# Front_Servo_Supply.net
KiCad netlist of a schematic drawn in Altium Designer
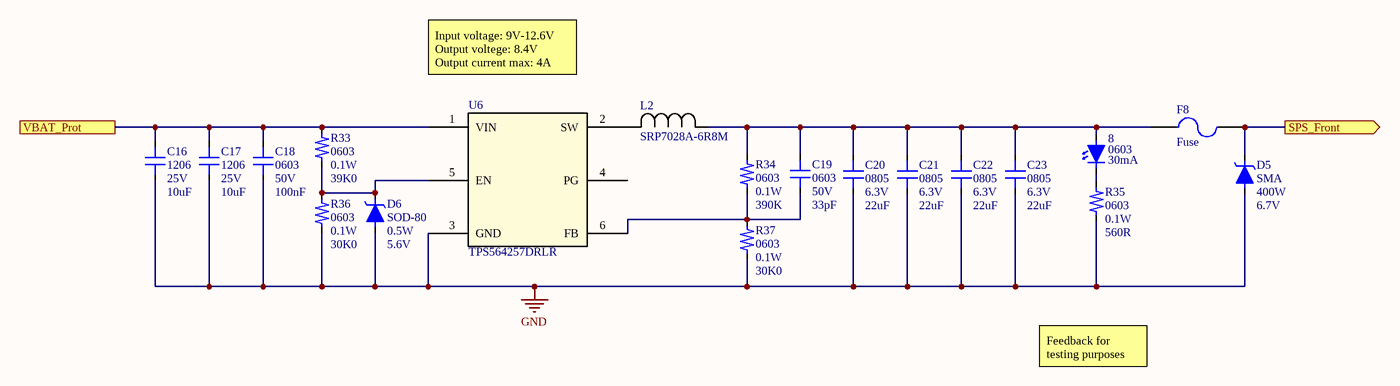
[diagram p0: Front_Servo_Supply.SchDoc]

(export (version "E")
  (design (tool "Eeschema 10.0.6"))
  (components
    (comp (ref "8")
      (value "0603")
      (footprint "LED_0603")
      (fields
        (field (name "PART NUMBER") "FYLS-0603UGC")
        (field (name "TOLERANCE") "5%")
        (field (name "RATING") "30mA")
      )
      (libsource (lib "Components") (part "Diode_LED"))
    )
    (comp (ref "C16")
      (value "1206")
      (footprint "C_1206")
      (fields
        (field (name "TOLERANCE") "10%")
        (field (name "PART NUMBER") "C3216X7R1E106K160AB")
        (field (name "RATING") "25V")
        (field (name "ALTIUM_VALUE") "10uF")
      )
      (libsource (lib "Components") (part "Capacitor_Chip"))
    )
    (comp (ref "C17")
      (value "1206")
      (footprint "C_1206")
      (fields
        (field (name "TOLERANCE") "10%")
        (field (name "PART NUMBER") "C3216X7R1E106K160AB")
        (field (name "RATING") "25V")
        (field (name "ALTIUM_VALUE") "10uF")
      )
      (libsource (lib "Components") (part "Capacitor_Chip"))
    )
    (comp (ref "C18")
      (value "0603")
      (footprint "C_0603")
      (fields
        (field (name "TOLERANCE") "10%")
        (field (name "PART NUMBER") "CC0603KRX7R9BB104")
        (field (name "RATING") "50V")
        (field (name "ALTIUM_VALUE") "100nF")
        (field (name "NI PART NUMBER") "716340-01")
      )
      (libsource (lib "Components") (part "Capacitor_Chip"))
    )
    (comp (ref "C19")
      (value "0603")
      (footprint "C_0603")
      (fields
        (field (name "TOLERANCE") "5%")
        (field (name "PART NUMBER") "CL10C330JB8NNNC")
        (field (name "RATING") "50V")
        (field (name "ALTIUM_VALUE") "33pF")
        (field (name "NI PART NUMBER") "715511-01")
      )
      (libsource (lib "Components") (part "Capacitor_Chip"))
    )
    (comp (ref "C20")
      (value "0805")
      (footprint "C_0805")
      (fields
        (field (name "TOLERANCE") "20%")
        (field (name "PART NUMBER") "CL21A226MQQNNNG")
        (field (name "RATING") "6.3V")
        (field (name "ALTIUM_VALUE") "22uF")
      )
      (libsource (lib "Components") (part "Capacitor_Chip"))
    )
    (comp (ref "C21")
      (value "0805")
      (footprint "C_0805")
      (fields
        (field (name "TOLERANCE") "20%")
        (field (name "PART NUMBER") "CL21A226MQQNNNG")
        (field (name "RATING") "6.3V")
        (field (name "ALTIUM_VALUE") "22uF")
      )
      (libsource (lib "Components") (part "Capacitor_Chip"))
    )
    (comp (ref "C22")
      (value "0805")
      (footprint "C_0805")
      (fields
        (field (name "TOLERANCE") "20%")
        (field (name "PART NUMBER") "CL21A226MQQNNNG")
        (field (name "RATING") "6.3V")
        (field (name "ALTIUM_VALUE") "22uF")
      )
      (libsource (lib "Components") (part "Capacitor_Chip"))
    )
    (comp (ref "C23")
      (value "0805")
      (footprint "C_0805")
      (fields
        (field (name "TOLERANCE") "20%")
        (field (name "PART NUMBER") "CL21A226MQQNNNG")
        (field (name "RATING") "6.3V")
        (field (name "ALTIUM_VALUE") "22uF")
      )
      (libsource (lib "Components") (part "Capacitor_Chip"))
    )
    (comp (ref "D5")
      (value "SMA")
      (footprint "SMA")
      (fields
        (field (name "PART NUMBER") "SMAJ5.0A")
        (field (name "TOLERANCE") "5%")
        (field (name "RATING") "400W")
        (field (name "ALTIUM_VALUE") "6.7V")
      )
      (libsource (lib "Components") (part "Diode_Transient_Sup"))
    )
    (comp (ref "D6")
      (value "SOD-80")
      (footprint "SOD-80")
      (fields
        (field (name "PART NUMBER") "BZV55C5V6")
        (field (name "RATING") "0.5W")
        (field (name "ALTIUM_VALUE") "5.6V")
      )
      (libsource (lib "Components") (part "Diode_Zener"))
    )
    (comp (ref "F8")
      (value "Fuse")
      (footprint "F_2410")
      (fields (field (name "PART NUMBER") "0451003.MRL"))
      (libsource (lib "Components") (part "Fuse"))
    )
    (comp (ref "L2")
      (value "SRP7028A-6R8M")
      (footprint "IND_SRP7028A-6R8M_BRN")
      (description "No Description Available")
      (fields (field (name "COPYRIGHT") "Copyright (C) 2023 Ultra Librarian. All rights reserved."))
      (libsource (lib "SRP7028A-6R8M") (part "SRP7028A-6R8M"))
    )
    (comp (ref "R33")
      (value "0603")
      (footprint "R_0603")
      (fields
        (field (name "TOLERANCE") "5%")
        (field (name "PART NUMBER") "CR-03JL7---39K")
        (field (name "RATING") "0.1W")
        (field (name "ALTIUM_VALUE") "39K0")
        (field (name "NI PART NUMBER") "613245-01")
      )
      (libsource (lib "Components") (part "Resistor_Chip"))
    )
    (comp (ref "R34")
      (value "0603")
      (footprint "R_0603")
      (fields
        (field (name "TOLERANCE") "1%")
        (field (name "PART NUMBER") "CR-03FL7--390K")
        (field (name "RATING") "0.1W")
        (field (name "ALTIUM_VALUE") "390K")
      )
      (libsource (lib "Components") (part "Resistor_Chip"))
    )
    (comp (ref "R35")
      (value "0603")
      (footprint "R_0603")
      (fields
        (field (name "TOLERANCE") "1%")
        (field (name "PART NUMBER") "CR-03FL7--560R")
        (field (name "RATING") "0.1W")
        (field (name "ALTIUM_VALUE") "560R")
        (field (name "NI PART NUMBER") "612556-01")
      )
      (libsource (lib "Components") (part "Resistor_Chip"))
    )
    (comp (ref "R36")
      (value "0603")
      (footprint "R_0603")
      (fields
        (field (name "TOLERANCE") "1%")
        (field (name "PART NUMBER") "CR-03FL7---30K")
        (field (name "RATING") "0.1W")
        (field (name "ALTIUM_VALUE") "30K0")
        (field (name "NI PART NUMBER") "612699-01")
      )
      (libsource (lib "Components") (part "Resistor_Chip"))
    )
    (comp (ref "R37")
      (value "0603")
      (footprint "R_0603")
      (fields
        (field (name "TOLERANCE") "1%")
        (field (name "PART NUMBER") "CR-03FL7---30K")
        (field (name "RATING") "0.1W")
        (field (name "ALTIUM_VALUE") "30K0")
        (field (name "NI PART NUMBER") "612699-01")
      )
      (libsource (lib "Components") (part "Resistor_Chip"))
    )
    (comp (ref "U6")
      (value "TPS564257DRLR")
      (footprint "TPS564242DRLR_TEX")
      (description "No Description Available")
      (fields (field (name "COPYRIGHT") "Copyright (C) 2023 Ultra Librarian. All rights reserved."))
      (libsource (lib "TPS564257DRLR") (part "TPS564257DRLR"))
    )
  )
  (nets
    (net (code "1") (name "/SPS_Front") (class "Default")
      (node (ref "D5") (pin "1") (pinfunction "DC_1") (pintype "passive"))
      (node (ref "F8") (pin "2") (pinfunction "2_2") (pintype "passive"))
    )
    (net (code "2") (name "/VBAT_Prot") (class "Default")
      (node (ref "C16") (pin "2") (pinfunction "C2_2") (pintype "passive"))
      (node (ref "C17") (pin "2") (pinfunction "C2_2") (pintype "passive"))
      (node (ref "C18") (pin "2") (pinfunction "C2_2") (pintype "passive"))
      (node (ref "R33") (pin "2") (pinfunction "R2_2") (pintype "passive"))
      (node (ref "U6") (pin "1") (pinfunction "VIN_1") (pintype "power_in"))
    )
    (net (code "3") (name "GND") (class "Default")
      (node (ref "C16") (pin "1") (pinfunction "C1_1") (pintype "passive"))
      (node (ref "C17") (pin "1") (pinfunction "C1_1") (pintype "passive"))
      (node (ref "C18") (pin "1") (pinfunction "C1_1") (pintype "passive"))
      (node (ref "C20") (pin "1") (pinfunction "C1_1") (pintype "passive"))
      (node (ref "C21") (pin "1") (pinfunction "C1_1") (pintype "passive"))
      (node (ref "C22") (pin "1") (pinfunction "C1_1") (pintype "passive"))
      (node (ref "C23") (pin "1") (pinfunction "C1_1") (pintype "passive"))
      (node (ref "D5") (pin "2") (pinfunction "DA_2") (pintype "passive"))
      (node (ref "D6") (pin "2") (pinfunction "DA_2") (pintype "passive"))
      (node (ref "R35") (pin "1") (pinfunction "R1_1") (pintype "passive"))
      (node (ref "R36") (pin "1") (pinfunction "R1_1") (pintype "passive"))
      (node (ref "R37") (pin "1") (pinfunction "R1_1") (pintype "passive"))
      (node (ref "U6") (pin "3") (pinfunction "GND_3") (pintype "power_in"))
    )
    (net (code "4") (name "Net-(8-DA)") (class "Default")
      (node (ref "8") (pin "2") (pinfunction "DA_2") (pintype "passive"))
      (node (ref "C19") (pin "2") (pinfunction "C2_2") (pintype "passive"))
      (node (ref "C20") (pin "2") (pinfunction "C2_2") (pintype "passive"))
      (node (ref "C21") (pin "2") (pinfunction "C2_2") (pintype "passive"))
      (node (ref "C22") (pin "2") (pinfunction "C2_2") (pintype "passive"))
      (node (ref "C23") (pin "2") (pinfunction "C2_2") (pintype "passive"))
      (node (ref "F8") (pin "1") (pinfunction "1_1") (pintype "passive"))
      (node (ref "L2") (pin "1") (pinfunction "1_1") (pintype "passive"))
      (node (ref "R34") (pin "2") (pinfunction "R2_2") (pintype "passive"))
    )
    (net (code "5") (name "Net-(8-DC)") (class "Default")
      (node (ref "8") (pin "1") (pinfunction "DC_1") (pintype "passive"))
      (node (ref "R35") (pin "2") (pinfunction "R2_2") (pintype "passive"))
    )
    (net (code "6") (name "Net-(C19-C1)") (class "Default")
      (node (ref "C19") (pin "1") (pinfunction "C1_1") (pintype "passive"))
      (node (ref "R34") (pin "1") (pinfunction "R1_1") (pintype "passive"))
      (node (ref "R37") (pin "2") (pinfunction "R2_2") (pintype "passive"))
      (node (ref "U6") (pin "6") (pinfunction "FB_6") (pintype "passive"))
    )
    (net (code "7") (name "Net-(D6-DC)") (class "Default")
      (node (ref "D6") (pin "1") (pinfunction "DC_1") (pintype "passive"))
      (node (ref "R33") (pin "1") (pinfunction "R1_1") (pintype "passive"))
      (node (ref "R36") (pin "2") (pinfunction "R2_2") (pintype "passive"))
      (node (ref "U6") (pin "5") (pinfunction "EN_5") (pintype "passive"))
    )
    (net (code "8") (name "Net-(U6-SW)") (class "Default")
      (node (ref "L2") (pin "2") (pinfunction "2_2") (pintype "passive"))
      (node (ref "U6") (pin "2") (pinfunction "SW_2") (pintype "power_in"))
    )
    (net (code "9") (name "unconnected-(U6-PG-Pad4)") (class "Default")
      (node (ref "U6") (pin "4") (pinfunction "PG_4") (pintype "passive"))
    )
  )
)
